# Sensor.net
KiCad netlist of a schematic drawn in EAGLE
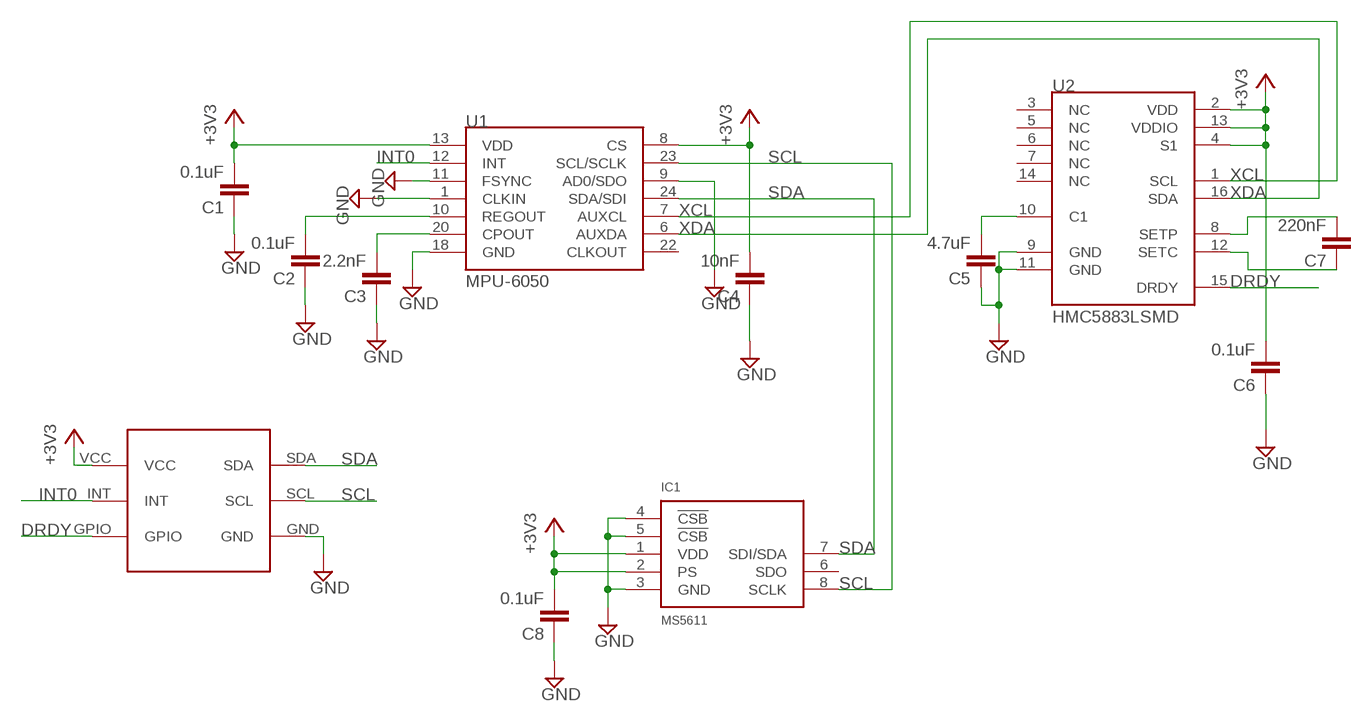
[diagram p0: schematic, sheet 1]

(export (version "E")
  (design (tool "Eeschema 10.0.6"))
  (components
    (comp (ref "C1")
      (value "0.1uF")
      (footprint "eagle-import:C0805")
      (libsource (lib "eagle-import") (part "C-EUC0805"))
    )
    (comp (ref "C2")
      (value "0.1uF")
      (footprint "eagle-import:C0805")
      (libsource (lib "eagle-import") (part "C-EUC0805"))
    )
    (comp (ref "C3")
      (value "2.2nF")
      (footprint "eagle-import:C0805")
      (libsource (lib "eagle-import") (part "C-EUC0805"))
    )
    (comp (ref "C4")
      (value "10nF")
      (footprint "eagle-import:C0805")
      (libsource (lib "eagle-import") (part "C-EUC0805"))
    )
    (comp (ref "C5")
      (value "4.7uF")
      (footprint "eagle-import:C0805")
      (libsource (lib "eagle-import") (part "C-EUC0805"))
    )
    (comp (ref "C6")
      (value "0.1uF")
      (footprint "eagle-import:C0805")
      (libsource (lib "eagle-import") (part "C-EUC0805"))
    )
    (comp (ref "C7")
      (value "220nF")
      (footprint "eagle-import:C0805")
      (libsource (lib "eagle-import") (part "C-EUC0805"))
    )
    (comp (ref "C8")
      (value "0.1uF")
      (footprint "eagle-import:C0805")
      (libsource (lib "eagle-import") (part "C-EUC0805"))
    )
    (comp (ref "IC1")
      (value "MS5611")
      (footprint "eagle-import:QFN-MS5611")
      (libsource (lib "eagle-import") (part "MS5611"))
    )
    (comp (ref "U$1")
      (value "SENSOR-BOARD")
      (footprint "eagle-import:SENSOR-BOARD")
      (libsource (lib "eagle-import") (part "SENSOR-BOARD"))
    )
    (comp (ref "U1")
      (value "MPU-6050")
      (footprint "eagle-import:QFN-24-TESTING")
      (libsource (lib "eagle-import") (part "MPU-6000QFN-24"))
    )
    (comp (ref "U2")
      (value "HMC5883LSMD")
      (footprint "eagle-import:16LPCC")
      (libsource (lib "eagle-import") (part "HMC5883LSMD"))
    )
  )
  (nets
    (net (code "1") (name "+3V3") (class "Default")
      (node (ref "C1") (pin "2") (pinfunction "2_2") (pintype "passive"))
      (node (ref "C4") (pin "2") (pinfunction "2_2") (pintype "passive"))
      (node (ref "C6") (pin "2") (pinfunction "2_2") (pintype "passive"))
      (node (ref "C8") (pin "2") (pinfunction "2_2") (pintype "passive"))
      (node (ref "IC1") (pin "1") (pinfunction "VDD_1") (pintype "bidirectional"))
      (node (ref "IC1") (pin "2") (pinfunction "PS_2") (pintype "bidirectional"))
      (node (ref "U$1") (pin "VCC") (pinfunction "VCC_VCC") (pintype "bidirectional"))
      (node (ref "U1") (pin "13") (pinfunction "VDD_13") (pintype "bidirectional"))
      (node (ref "U1") (pin "8") (pinfunction "CS_8") (pintype "bidirectional"))
      (node (ref "U2") (pin "13") (pinfunction "VDDIO_13") (pintype "bidirectional"))
      (node (ref "U2") (pin "2") (pinfunction "VDD_2") (pintype "bidirectional"))
      (node (ref "U2") (pin "4") (pinfunction "S1_4") (pintype "bidirectional"))
    )
    (net (code "2") (name "/DRDY") (class "Default")
      (node (ref "U$1") (pin "GPIO") (pinfunction "GPIO_GPIO") (pintype "bidirectional"))
      (node (ref "U2") (pin "15") (pinfunction "DRDY_15") (pintype "bidirectional"))
    )
    (net (code "3") (name "/INT0") (class "Default")
      (node (ref "U$1") (pin "INT") (pinfunction "INT_INT") (pintype "bidirectional"))
      (node (ref "U1") (pin "12") (pinfunction "INT_12") (pintype "bidirectional"))
    )
    (net (code "4") (name "/SCL") (class "Default")
      (node (ref "IC1") (pin "8") (pinfunction "SCLK_8") (pintype "bidirectional"))
      (node (ref "U$1") (pin "SCL") (pinfunction "SCL_SCL") (pintype "bidirectional"))
      (node (ref "U1") (pin "23") (pinfunction "SCL/SCLK_23") (pintype "bidirectional"))
    )
    (net (code "5") (name "/SDA") (class "Default")
      (node (ref "IC1") (pin "7") (pinfunction "SDI/SDA_7") (pintype "bidirectional"))
      (node (ref "U$1") (pin "SDA") (pinfunction "SDA_SDA") (pintype "bidirectional"))
      (node (ref "U1") (pin "24") (pinfunction "SDA/SDI_24") (pintype "bidirectional"))
    )
    (net (code "6") (name "/XCL") (class "Default")
      (node (ref "U1") (pin "7") (pinfunction "AUXCL_7") (pintype "bidirectional"))
      (node (ref "U2") (pin "1") (pinfunction "SCL_1") (pintype "bidirectional"))
    )
    (net (code "7") (name "/XDA") (class "Default")
      (node (ref "U1") (pin "6") (pinfunction "AUXDA_6") (pintype "bidirectional"))
      (node (ref "U2") (pin "16") (pinfunction "SDA_16") (pintype "bidirectional"))
    )
    (net (code "8") (name "GND") (class "Default")
      (node (ref "C1") (pin "1") (pinfunction "1_1") (pintype "passive"))
      (node (ref "C2") (pin "1") (pinfunction "1_1") (pintype "passive"))
      (node (ref "C3") (pin "1") (pinfunction "1_1") (pintype "passive"))
      (node (ref "C4") (pin "1") (pinfunction "1_1") (pintype "passive"))
      (node (ref "C5") (pin "1") (pinfunction "1_1") (pintype "passive"))
      (node (ref "C6") (pin "1") (pinfunction "1_1") (pintype "passive"))
      (node (ref "C8") (pin "1") (pinfunction "1_1") (pintype "passive"))
      (node (ref "IC1") (pin "3") (pinfunction "GND_3") (pintype "bidirectional"))
      (node (ref "IC1") (pin "4") (pinfunction "~{CSB}_4") (pintype "bidirectional"))
      (node (ref "IC1") (pin "5") (pinfunction "~{CSB}_5") (pintype "bidirectional"))
      (node (ref "U$1") (pin "GND") (pinfunction "GND_GND") (pintype "bidirectional"))
      (node (ref "U1") (pin "1") (pinfunction "CLKIN_1") (pintype "bidirectional"))
      (node (ref "U1") (pin "11") (pinfunction "FSYNC_11") (pintype "bidirectional"))
      (node (ref "U1") (pin "18") (pinfunction "GND_18") (pintype "bidirectional"))
      (node (ref "U1") (pin "9") (pinfunction "AD0/SDO_9") (pintype "bidirectional"))
      (node (ref "U2") (pin "11") (pinfunction "GND_11") (pintype "bidirectional"))
      (node (ref "U2") (pin "9") (pinfunction "GND_9") (pintype "bidirectional"))
    )
    (net (code "9") (name "Net-(U1-CPOUT)") (class "Default")
      (node (ref "C3") (pin "2") (pinfunction "2_2") (pintype "passive"))
      (node (ref "U1") (pin "20") (pinfunction "CPOUT_20") (pintype "bidirectional"))
    )
    (net (code "10") (name "Net-(U1-REGOUT)") (class "Default")
      (node (ref "C2") (pin "2") (pinfunction "2_2") (pintype "passive"))
      (node (ref "U1") (pin "10") (pinfunction "REGOUT_10") (pintype "bidirectional"))
    )
    (net (code "11") (name "Net-(U2-C1)") (class "Default")
      (node (ref "C5") (pin "2") (pinfunction "2_2") (pintype "passive"))
      (node (ref "U2") (pin "10") (pinfunction "C1_10") (pintype "bidirectional"))
    )
    (net (code "12") (name "Net-(U2-SETC)") (class "Default")
      (node (ref "C7") (pin "1") (pinfunction "1_1") (pintype "passive"))
      (node (ref "U2") (pin "12") (pinfunction "SETC_12") (pintype "bidirectional"))
    )
    (net (code "13") (name "Net-(U2-SETP)") (class "Default")
      (node (ref "C7") (pin "2") (pinfunction "2_2") (pintype "passive"))
      (node (ref "U2") (pin "8") (pinfunction "SETP_8") (pintype "bidirectional"))
    )
    (net (code "14") (name "unconnected-(IC1-SDO-Pad6)") (class "Default")
      (node (ref "IC1") (pin "6") (pinfunction "SDO_6") (pintype "bidirectional"))
    )
    (net (code "15") (name "unconnected-(U1-CLKOUT-Pad22)") (class "Default")
      (node (ref "U1") (pin "22") (pinfunction "CLKOUT_22") (pintype "bidirectional"))
    )
    (net (code "16") (name "unconnected-(U2-NC-Pad3)") (class "Default")
      (node (ref "U2") (pin "3") (pinfunction "NC_3") (pintype "bidirectional"))
    )
    (net (code "17") (name "unconnected-(U2-NC-Pad5)") (class "Default")
      (node (ref "U2") (pin "5") (pinfunction "NC_5") (pintype "bidirectional"))
    )
    (net (code "18") (name "unconnected-(U2-NC-Pad6)") (class "Default")
      (node (ref "U2") (pin "6") (pinfunction "NC_6") (pintype "bidirectional"))
    )
    (net (code "19") (name "unconnected-(U2-NC-Pad7)") (class "Default")
      (node (ref "U2") (pin "7") (pinfunction "NC_7") (pintype "bidirectional"))
    )
    (net (code "20") (name "unconnected-(U2-NC-Pad14)") (class "Default")
      (node (ref "U2") (pin "14") (pinfunction "NC_14") (pintype "bidirectional"))
    )
  )
)
